# SUBBOARD-gate_driver.net
KiCad netlist of a schematic drawn in Altium Designer
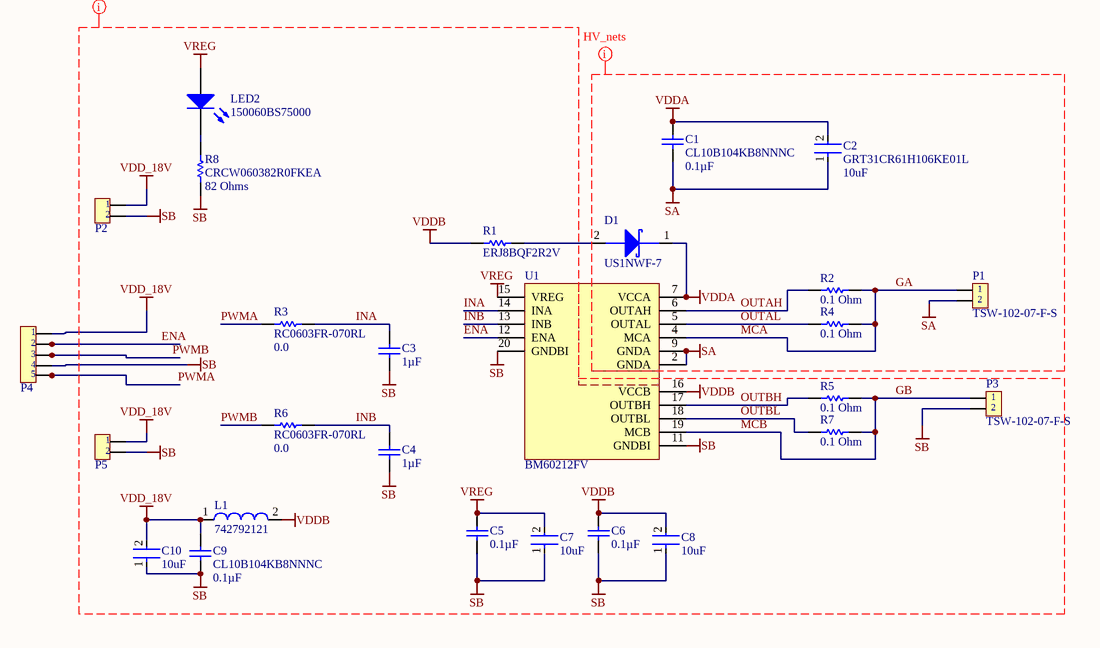
[diagram p0: SUBBOARD-gate_driver.SchDoc]

(export (version "E")
  (design (tool "Eeschema 10.0.6"))
  (components
    (comp (ref "C1")
      (value "CL10B104KB8NNNC")
      (footprint "SAMS-C0603-2_L")
      (description "Multi-layer Ceramic Capacitor, -55 to 125 degC, 2-Pin SMD (0603), RoHS, Tape and Reel")
      (fields (field (name "CAPACITANCE") "0.1µF") (field (name "MANUFACTURER") "Samsung Electro-Mechanics"))
      (libsource (lib "Altium Content Vault") (part "CAP-NP-2"))
    )
    (comp (ref "C2")
      (value "GRT31CR61H106KE01L")
      (footprint "FP-GRT31-0_2-MFG")
      (description "CAP CER 10UF 50V X5R 1206")
      (fields
        (field (name "TOLERANCE") "10%")
        (field (name "OCTOPART") "https://octopart.com/grt31cr61h106ke01l-murata-62921736")
        (field (name "ALTIUM_VALUE") "10uF")
      )
      (libsource (lib "Altium Content Vault") (part "11868f565c42a9108669ba33697ecf6"))
    )
    (comp (ref "C3")
      (value "LMK107B7105KA-T")
      (footprint "CAPC1608X90X35LL10T25")
      (fields
        (field (name "CAPACITANCE") "1µF")
        (field (name "TOLERANCE") "±10%")
        (field (name "MANUFACTURER") "Taiyo Yuden")
        (field (name "PCN PART NUMBER") "X5R,X7RDielectrics23/Jan/2008")
      )
      (libsource (lib "Altium Content Vault") (part "CAP-NP-2"))
    )
    (comp (ref "C4")
      (value "LMK107B7105KA-T")
      (footprint "CAPC1608X90X35LL10T25")
      (fields
        (field (name "CAPACITANCE") "1µF")
        (field (name "TOLERANCE") "±10%")
        (field (name "MANUFACTURER") "Taiyo Yuden")
        (field (name "PCN PART NUMBER") "X5R,X7RDielectrics23/Jan/2008")
      )
      (libsource (lib "Altium Content Vault") (part "CAP-NP-2"))
    )
    (comp (ref "C5")
      (value "CL10B104KB8NNNC")
      (footprint "SAMS-C0603-2_L")
      (description "Multi-layer Ceramic Capacitor, -55 to 125 degC, 2-Pin SMD (0603), RoHS, Tape and Reel")
      (fields (field (name "CAPACITANCE") "0.1µF") (field (name "MANUFACTURER") "Samsung Electro-Mechanics"))
      (libsource (lib "Altium Content Vault") (part "CAP-NP-2"))
    )
    (comp (ref "C6")
      (value "CL10B104KB8NNNC")
      (footprint "SAMS-C0603-2_L")
      (description "Multi-layer Ceramic Capacitor, -55 to 125 degC, 2-Pin SMD (0603), RoHS, Tape and Reel")
      (fields (field (name "CAPACITANCE") "0.1µF") (field (name "MANUFACTURER") "Samsung Electro-Mechanics"))
      (libsource (lib "Altium Content Vault") (part "CAP-NP-2"))
    )
    (comp (ref "C7")
      (value "10uF")
      (footprint "FP-GRT31-0_2-MFG")
      (description "CAP CER 10UF 50V X5R 1206")
      (fields
        (field (name "TOLERANCE") "10%")
        (field (name "OCTOPART") "https://octopart.com/grt31cr61h106ke01l-murata-62921736")
      )
      (libsource (lib "Altium Content Vault") (part "11868f565c42a9108669ba33697ecf6"))
    )
    (comp (ref "C8")
      (value "10uF")
      (footprint "FP-GRT31-0_2-MFG")
      (description "CAP CER 10UF 50V X5R 1206")
      (fields
        (field (name "TOLERANCE") "10%")
        (field (name "OCTOPART") "https://octopart.com/grt31cr61h106ke01l-murata-62921736")
      )
      (libsource (lib "Altium Content Vault") (part "11868f565c42a9108669ba33697ecf6"))
    )
    (comp (ref "C9")
      (value "CL10B104KB8NNNC")
      (footprint "SAMS-C0603-2_L")
      (description "Multi-layer Ceramic Capacitor, -55 to 125 degC, 2-Pin SMD (0603), RoHS, Tape and Reel")
      (fields (field (name "CAPACITANCE") "0.1µF") (field (name "MANUFACTURER") "Samsung Electro-Mechanics"))
      (libsource (lib "Altium Content Vault") (part "CAP-NP-2"))
    )
    (comp (ref "C10")
      (value "10uF")
      (footprint "FP-GRT31-0_2-MFG")
      (description "CAP CER 10UF 50V X5R 1206")
      (fields
        (field (name "TOLERANCE") "10%")
        (field (name "OCTOPART") "https://octopart.com/grt31cr61h106ke01l-murata-62921736")
      )
      (libsource (lib "Altium Content Vault") (part "11868f565c42a9108669ba33697ecf6"))
    )
    (comp (ref "D1")
      (value "US1NWF-7")
      (footprint "SOD123F")
      (description "DIODE GEN PURP 1.2KV 1A SOD123F")
      (fields (field (name "MANUFACTURER") "Diodes"))
      (libsource (lib "Altium_Library_POWERLAB") (part "US1NWF-7"))
    )
    (comp (ref "L1")
      (value "742792121")
      (footprint "SMD-1206")
      (description "SMD EMI Suppression Ferrite Bead WE-CBF, Z = 300 Ohm")
      (libsource (lib "Altium Content Vault") (part "PAS-IND-INDUCTOR-2"))
    )
    (comp (ref "LED2")
      (value "150060BS75000")
      (footprint "0603_A")
      (description "SMD mono-color Chip LED, WL-SMCW, Blue")
      (fields (field (name "MANUFACTURER") "Wuerth Elektronik"))
      (libsource (lib "Altium Content Vault") (part "WE-LED_K1A2-2"))
    )
    (comp (ref "P1")
      (value "TSW-102-07-F-S")
      (footprint "TSW-102-07-F-S")
      (description "Conn Unshrouded Header HDR 2 POS 2.54mm Solder ST Thru-Hole")
      (fields (field (name "MANUFACTURER") "Samtec"))
      (libsource (lib "Altium_Library_POWERLAB") (part "TSW-102-07-F-S"))
    )
    (comp (ref "P2")
      (value "TSW-102-05-G-S")
      (footprint "TSW-102-05-G-S")
      (description "Conn Unshrouded Header HDR 2 POS 2.54mm Solder ST Thru-Hole Automotive Bulk")
      (fields (field (name "MANUFACTURER") "Samtec"))
      (libsource (lib "Altium_Library_POWERLAB") (part "TSW-102-05-G-S"))
    )
    (comp (ref "P3")
      (value "TSW-102-07-F-S")
      (footprint "TSW-102-07-F-S")
      (description "Conn Unshrouded Header HDR 2 POS 2.54mm Solder ST Thru-Hole")
      (fields (field (name "MANUFACTURER") "Samtec"))
      (libsource (lib "Altium_Library_POWERLAB") (part "TSW-102-07-F-S"))
    )
    (comp (ref "P4")
      (value "TSW-105-07-G-S")
      (footprint "TSW-105-07-G-S")
      (fields (field (name "MANUFACTURER") "Samtec"))
      (libsource (lib "Altium_Library_POWERLAB") (part "TSW-105-07-G-S"))
    )
    (comp (ref "P5")
      (value "TSW-102-05-G-S")
      (footprint "TSW-102-05-G-S")
      (description "Conn Unshrouded Header HDR 2 POS 2.54mm Solder ST Thru-Hole Automotive Bulk")
      (fields (field (name "MANUFACTURER") "Samtec"))
      (libsource (lib "Altium_Library_POWERLAB") (part "TSW-102-05-G-S"))
    )
    (comp (ref "R1")
      (value "ERJ8BQF2R2V")
      (footprint "RESC3216X70X50NL05T20")
      (fields (field (name "MANUFACTURER") "Panasonic"))
      (libsource (lib "Altium Content Vault") (part "RES"))
    )
    (comp (ref "R2")
      (value "0.1 Ohm")
      (footprint "RESC3216X70X50LL05T20")
      (fields (field (name "MANUFACTURER") "Panasonic") (field (name "PART NUMBER") "ERJ8BWFR100V"))
      (libsource (lib "Altium Content Vault") (part "RES"))
    )
    (comp (ref "R3")
      (value "RC0603FR-070RL")
      (footprint "RESC1608X55X25LL10T15")
      (description "Chip Resistor, 0 Ohm, +/- 1%, 100 mW, -55 to 155 degC, 0603 (1608 Metric), RoHS, Tape and Reel")
      (fields
        (field (name "RESISTANCE (OHMS)") "0.0")
        (field (name "MANUFACTURER") "Yageo")
        (field (name "TOLERANCE") "Jumper")
      )
      (libsource (lib "Altium Content Vault") (part "RES-2"))
    )
    (comp (ref "R4")
      (value "0.1 Ohm")
      (footprint "RESC3216X70X50LL05T20")
      (fields (field (name "MANUFACTURER") "Panasonic") (field (name "PART NUMBER") "ERJ8BWFR100V"))
      (libsource (lib "Altium Content Vault") (part "RES"))
    )
    (comp (ref "R5")
      (value "0.1 Ohm")
      (footprint "RESC3216X70X50LL05T20")
      (fields (field (name "MANUFACTURER") "Panasonic") (field (name "PART NUMBER") "ERJ8BWFR100V"))
      (libsource (lib "Altium Content Vault") (part "RES"))
    )
    (comp (ref "R6")
      (value "RC0603FR-070RL")
      (footprint "RESC1608X55X25LL10T15")
      (description "Chip Resistor, 0 Ohm, +/- 1%, 100 mW, -55 to 155 degC, 0603 (1608 Metric), RoHS, Tape and Reel")
      (fields
        (field (name "RESISTANCE (OHMS)") "0.0")
        (field (name "MANUFACTURER") "Yageo")
        (field (name "TOLERANCE") "Jumper")
      )
      (libsource (lib "Altium Content Vault") (part "RES-2"))
    )
    (comp (ref "R7")
      (value "0.1 Ohm")
      (footprint "RESC3216X70X50LL05T20")
      (fields (field (name "MANUFACTURER") "Panasonic") (field (name "PART NUMBER") "ERJ8BWFR100V"))
      (libsource (lib "Altium Content Vault") (part "RES"))
    )
    (comp (ref "R8")
      (value "CRCW060382R0FKEA")
      (footprint "RESC1609X50X30LL10T20")
      (fields (field (name "MANUFACTURER") "Vishay Dale") (field (name "ALTIUM_VALUE") "82 Ohms"))
      (libsource (lib "Altium Content Vault") (part "RES"))
    )
    (comp (ref "U1")
      (value "BM60212FV")
      (footprint "SOP65P810X190-20N")
      (description "MOSFET and Power Driver 2-OUT Hi/Lo Side Non-Inv 20-Pin SSOP-BW Emboss T/R")
      (fields (field (name "MANUFACTURER") "Rohm") (field (name "MANUFACTURER PART NUMBER") "BM60212FV-CE2"))
      (libsource (lib "Altium_Library_POWERLAB") (part "BM60212FV-CE2"))
    )
  )
  (nets
    (net (code "1") (name "/ENA") (class "Default")
      (node (ref "P4") (pin "2") (pinfunction "2_2") (pintype "passive"))
      (node (ref "U1") (pin "12") (pinfunction "ENA_12") (pintype "passive"))
    )
    (net (code "2") (name "/GA") (class "Default")
      (node (ref "P1") (pin "1") (pinfunction "1_1") (pintype "passive"))
      (node (ref "R2") (pin "1") (pinfunction "1_1") (pintype "passive"))
      (node (ref "R4") (pin "1") (pinfunction "1_1") (pintype "passive"))
      (node (ref "U1") (pin "4") (pinfunction "MCA_4") (pintype "passive"))
    )
    (net (code "3") (name "/GB") (class "Default")
      (node (ref "P3") (pin "1") (pinfunction "1_1") (pintype "passive"))
      (node (ref "R5") (pin "1") (pinfunction "1_1") (pintype "passive"))
      (node (ref "R7") (pin "1") (pinfunction "1_1") (pintype "passive"))
      (node (ref "U1") (pin "19") (pinfunction "MCB_19") (pintype "passive"))
    )
    (net (code "4") (name "/INA") (class "Default")
      (node (ref "C3") (pin "1") (pinfunction "1_1") (pintype "passive"))
      (node (ref "R3") (pin "1") (pinfunction "1_1") (pintype "passive"))
      (node (ref "U1") (pin "14") (pinfunction "INA_14") (pintype "passive"))
    )
    (net (code "5") (name "/INB") (class "Default")
      (node (ref "C4") (pin "1") (pinfunction "1_1") (pintype "passive"))
      (node (ref "R6") (pin "1") (pinfunction "1_1") (pintype "passive"))
      (node (ref "U1") (pin "13") (pinfunction "INB_13") (pintype "passive"))
    )
    (net (code "6") (name "/OUTAH") (class "Default")
      (node (ref "R2") (pin "2") (pinfunction "2_2") (pintype "passive"))
      (node (ref "U1") (pin "6") (pinfunction "OUTAH_6") (pintype "passive"))
    )
    (net (code "7") (name "/OUTAL") (class "Default")
      (node (ref "R4") (pin "2") (pinfunction "2_2") (pintype "passive"))
      (node (ref "U1") (pin "5") (pinfunction "OUTAL_5") (pintype "passive"))
    )
    (net (code "8") (name "/OUTBH") (class "Default")
      (node (ref "R5") (pin "2") (pinfunction "2_2") (pintype "passive"))
      (node (ref "U1") (pin "17") (pinfunction "OUTBH_17") (pintype "passive"))
    )
    (net (code "9") (name "/OUTBL") (class "Default")
      (node (ref "R7") (pin "2") (pinfunction "2_2") (pintype "passive"))
      (node (ref "U1") (pin "18") (pinfunction "OUTBL_18") (pintype "passive"))
    )
    (net (code "10") (name "/PWMA") (class "Default")
      (node (ref "P4") (pin "5") (pinfunction "5_5") (pintype "passive"))
      (node (ref "R3") (pin "2") (pinfunction "2_2") (pintype "passive"))
    )
    (net (code "11") (name "/PWMB") (class "Default")
      (node (ref "P4") (pin "3") (pinfunction "3_3") (pintype "passive"))
      (node (ref "R6") (pin "2") (pinfunction "2_2") (pintype "passive"))
    )
    (net (code "12") (name "Net-(D1-Anode)") (class "Default")
      (node (ref "D1") (pin "2") (pinfunction "Anode_2") (pintype "passive"))
      (node (ref "R1") (pin "2") (pinfunction "2_2") (pintype "passive"))
    )
    (net (code "13") (name "Net-(LED2-K)") (class "Default")
      (node (ref "LED2") (pin "1") (pinfunction "K_1") (pintype "passive"))
      (node (ref "R8") (pin "1") (pinfunction "1_1") (pintype "passive"))
    )
    (net (code "14") (name "SA") (class "Default")
      (node (ref "C1") (pin "2") (pinfunction "2_2") (pintype "passive"))
      (node (ref "C2") (pin "1") (pinfunction "1_1") (pintype "passive"))
      (node (ref "P1") (pin "2") (pinfunction "2_2") (pintype "passive"))
      (node (ref "U1") (pin "2") (pinfunction "GNDA_2") (pintype "passive"))
      (node (ref "U1") (pin "9") (pinfunction "GNDA_9") (pintype "passive"))
    )
    (net (code "15") (name "SB") (class "Default")
      (node (ref "C10") (pin "1") (pinfunction "1_1") (pintype "passive"))
      (node (ref "C3") (pin "2") (pinfunction "2_2") (pintype "passive"))
      (node (ref "C4") (pin "2") (pinfunction "2_2") (pintype "passive"))
      (node (ref "C5") (pin "2") (pinfunction "2_2") (pintype "passive"))
      (node (ref "C6") (pin "2") (pinfunction "2_2") (pintype "passive"))
      (node (ref "C7") (pin "1") (pinfunction "1_1") (pintype "passive"))
      (node (ref "C8") (pin "1") (pinfunction "1_1") (pintype "passive"))
      (node (ref "C9") (pin "2") (pinfunction "2_2") (pintype "passive"))
      (node (ref "P2") (pin "2") (pinfunction "2_2") (pintype "passive"))
      (node (ref "P3") (pin "2") (pinfunction "2_2") (pintype "passive"))
      (node (ref "P4") (pin "4") (pinfunction "4_4") (pintype "passive"))
      (node (ref "P5") (pin "2") (pinfunction "2_2") (pintype "passive"))
      (node (ref "R8") (pin "2") (pinfunction "2_2") (pintype "passive"))
      (node (ref "U1") (pin "11") (pinfunction "GNDBI_11") (pintype "passive"))
      (node (ref "U1") (pin "20") (pinfunction "GNDBI_20") (pintype "passive"))
    )
    (net (code "16") (name "VDDA") (class "Default")
      (node (ref "C1") (pin "1") (pinfunction "1_1") (pintype "passive"))
      (node (ref "C2") (pin "2") (pinfunction "2_2") (pintype "passive"))
      (node (ref "D1") (pin "1") (pinfunction "Cathode_1") (pintype "passive"))
      (node (ref "U1") (pin "7") (pinfunction "VCCA_7") (pintype "passive"))
    )
    (net (code "17") (name "VDDB") (class "Default")
      (node (ref "C6") (pin "1") (pinfunction "1_1") (pintype "passive"))
      (node (ref "C8") (pin "2") (pinfunction "2_2") (pintype "passive"))
      (node (ref "L1") (pin "2") (pinfunction "2_2") (pintype "passive"))
      (node (ref "R1") (pin "1") (pinfunction "1_1") (pintype "passive"))
      (node (ref "U1") (pin "16") (pinfunction "VCCB_16") (pintype "passive"))
    )
    (net (code "18") (name "VDD_18V") (class "Default")
      (node (ref "C10") (pin "2") (pinfunction "2_2") (pintype "passive"))
      (node (ref "C9") (pin "1") (pinfunction "1_1") (pintype "passive"))
      (node (ref "L1") (pin "1") (pinfunction "1_1") (pintype "passive"))
      (node (ref "P2") (pin "1") (pinfunction "1_1") (pintype "passive"))
      (node (ref "P4") (pin "1") (pinfunction "1_1") (pintype "passive"))
      (node (ref "P5") (pin "1") (pinfunction "1_1") (pintype "passive"))
    )
    (net (code "19") (name "VREG") (class "Default")
      (node (ref "C5") (pin "1") (pinfunction "1_1") (pintype "passive"))
      (node (ref "C7") (pin "2") (pinfunction "2_2") (pintype "passive"))
      (node (ref "LED2") (pin "2") (pinfunction "A_2") (pintype "passive"))
      (node (ref "U1") (pin "15") (pinfunction "VREG_15") (pintype "passive"))
    )
  )
)
